# lb-charDisp-topLevel.net
KiCad netlist of a schematic drawn in Altium Designer
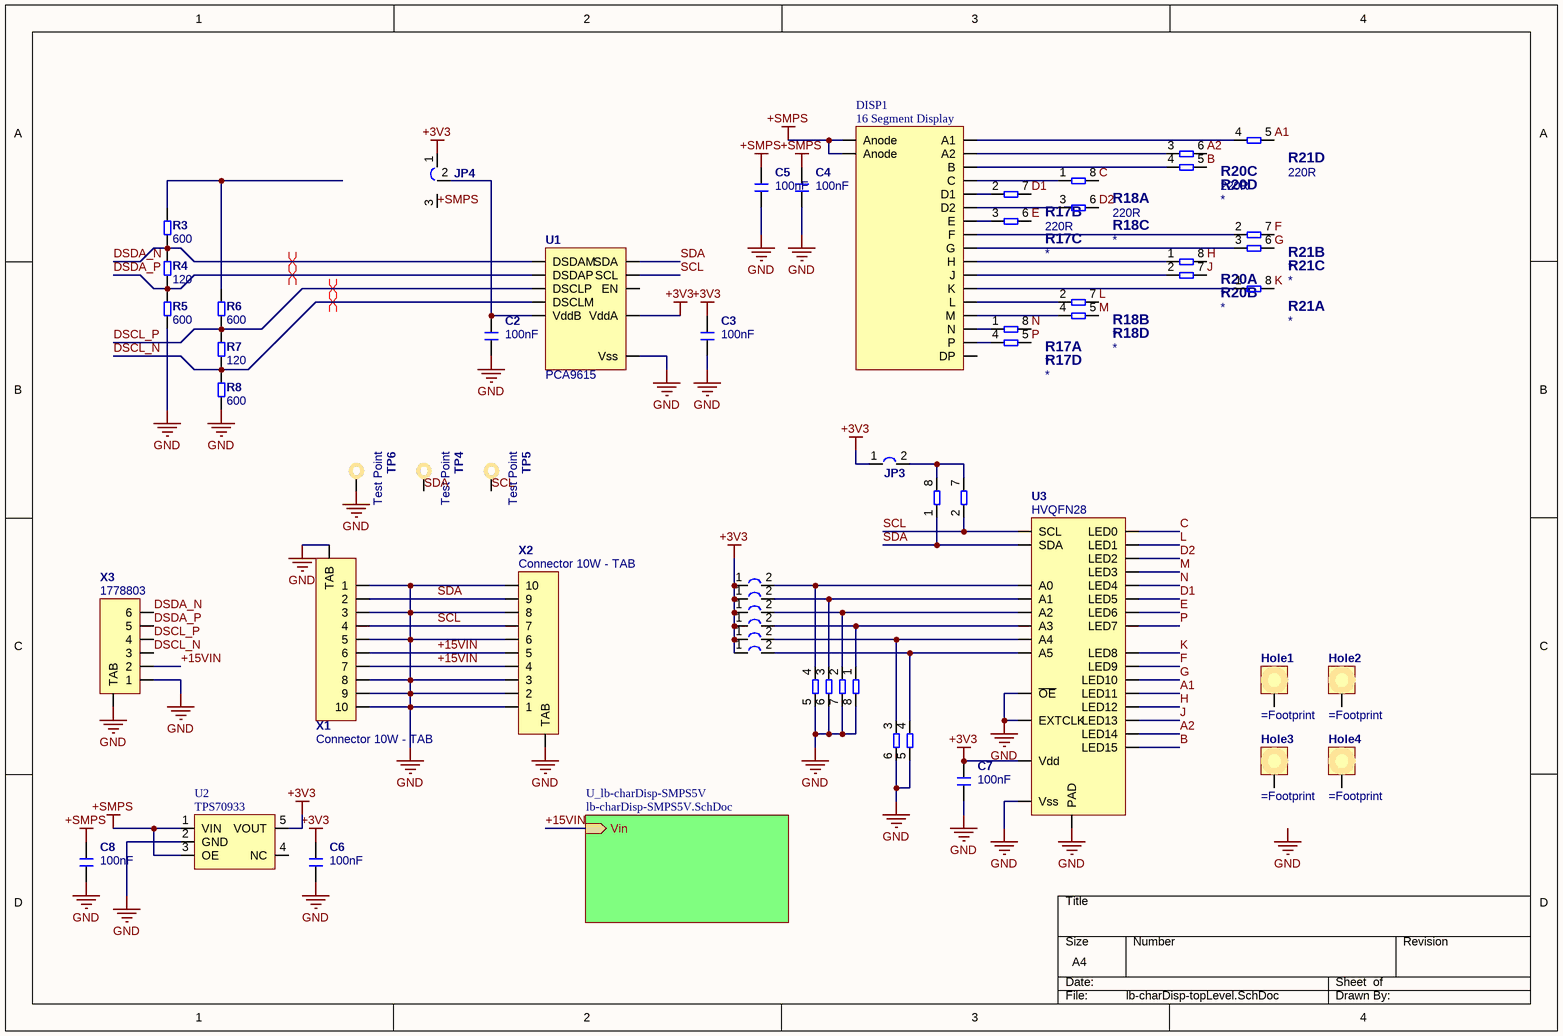
[diagram p0: lb-charDisp-topLevel.SchDoc]

(export (version "E")
  (design (tool "Eeschema 10.0.6"))
  (components
    (comp (ref "C2")
      (value "100nF")
      (footprint "C0603_N")
      (description "Capacitor MLCC")
      (fields
        (field (name "MANUFACTURER") "Yageo")
        (field (name "MANUFACTURER PART NUMBER") "CC0603KRX7R9BB104")
      )
      (libsource (lib "wes") (part "Capacitor"))
    )
    (comp (ref "C3")
      (value "100nF")
      (footprint "C0603_N")
      (description "Capacitor MLCC")
      (fields
        (field (name "MANUFACTURER") "Yageo")
        (field (name "MANUFACTURER PART NUMBER") "CC0603KRX7R9BB104")
      )
      (libsource (lib "wes") (part "Capacitor"))
    )
    (comp (ref "C4")
      (value "100nF")
      (footprint "C0603_N")
      (description "Capacitor MLCC")
      (fields
        (field (name "MANUFACTURER") "Yageo")
        (field (name "MANUFACTURER PART NUMBER") "CC0603KRX7R9BB104")
      )
      (libsource (lib "wes") (part "Capacitor"))
    )
    (comp (ref "C5")
      (value "100nF")
      (footprint "C0603_N")
      (description "Capacitor MLCC")
      (fields
        (field (name "MANUFACTURER") "Yageo")
        (field (name "MANUFACTURER PART NUMBER") "CC0603KRX7R9BB104")
      )
      (libsource (lib "wes") (part "Capacitor"))
    )
    (comp (ref "C6")
      (value "100nF")
      (footprint "C0603_N")
      (description "Capacitor MLCC")
      (fields
        (field (name "MANUFACTURER") "Yageo")
        (field (name "MANUFACTURER PART NUMBER") "CC0603KRX7R9BB104")
      )
      (libsource (lib "wes") (part "Capacitor"))
    )
    (comp (ref "C7")
      (value "100nF")
      (footprint "C0603_N")
      (description "Capacitor MLCC")
      (fields
        (field (name "MANUFACTURER") "Yageo")
        (field (name "MANUFACTURER PART NUMBER") "CC0603KRX7R9BB104")
      )
      (libsource (lib "wes") (part "Capacitor"))
    )
    (comp (ref "C8")
      (value "100nF")
      (footprint "C0603_N")
      (description "Capacitor MLCC")
      (fields
        (field (name "MANUFACTURER") "Yageo")
        (field (name "MANUFACTURER PART NUMBER") "CC0603KRX7R9BB104")
      )
      (libsource (lib "wes") (part "Capacitor"))
    )
    (comp (ref "DISP1")
      (value "16 Segment Display")
      (footprint "PSA23-11SRWA")
      (libsource (lib "wes") (part "Display 16 Segment"))
    )
    (comp (ref "Hole1") (value "~") (footprint "Insert-Thread-SMD-M2") (libsource (lib "wes") (part "Hole")))
    (comp (ref "Hole2") (value "~") (footprint "Insert-Thread-SMD-M2") (libsource (lib "wes") (part "Hole")))
    (comp (ref "Hole3") (value "~") (footprint "Insert-Thread-SMD-M2") (libsource (lib "wes") (part "Hole")))
    (comp (ref "Hole4") (value "~") (footprint "Insert-Thread-SMD-M2") (libsource (lib "wes") (part "Hole")))
    (comp (ref "JP3")
      (value "Jumper 2W")
      (footprint "Jumper SMD 2W NO")
      (libsource (lib "wes") (part "Jumper 2W"))
    )
    (comp (ref "JP4")
      (value "Jumper 3W")
      (footprint "Jumper SMD 3W NO")
      (libsource (lib "wes") (part "Jumper 3W"))
    )
    (comp (ref "JP_A0")
      (value "Jumper 2W")
      (footprint "Jumper SMD 2W NO")
      (libsource (lib "wes") (part "Jumper 2W"))
    )
    (comp (ref "JP_A1")
      (value "Jumper 2W")
      (footprint "Jumper SMD 2W NO")
      (libsource (lib "wes") (part "Jumper 2W"))
    )
    (comp (ref "JP_A2")
      (value "Jumper 2W")
      (footprint "Jumper SMD 2W NO")
      (libsource (lib "wes") (part "Jumper 2W"))
    )
    (comp (ref "JP_A3")
      (value "Jumper 2W")
      (footprint "Jumper SMD 2W NO")
      (libsource (lib "wes") (part "Jumper 2W"))
    )
    (comp (ref "JP_A4")
      (value "Jumper 2W")
      (footprint "Jumper SMD 2W NO")
      (libsource (lib "wes") (part "Jumper 2W"))
    )
    (comp (ref "JP_A5")
      (value "Jumper 2W")
      (footprint "Jumper SMD 2W NO")
      (libsource (lib "wes") (part "Jumper 2W"))
    )
    (comp (ref "R1") (value "; 4k7") (footprint "YC164") (libsource (lib "wes") (part "Resistor Array - 4P")))
    (comp (ref "R2") (value "; 4k7") (footprint "YC164") (libsource (lib "wes") (part "Resistor Array - 4P")))
    (comp (ref "R3")
      (value "600")
      (footprint "R0603")
      (fields (field (name "PUBLISHER") "Altium Limited"))
      (libsource (lib "wes") (part "Resistor"))
    )
    (comp (ref "R4")
      (value "120")
      (footprint "R0603")
      (fields (field (name "PUBLISHER") "Altium Limited"))
      (libsource (lib "wes") (part "Resistor"))
    )
    (comp (ref "R5")
      (value "600")
      (footprint "R0603")
      (fields (field (name "PUBLISHER") "Altium Limited"))
      (libsource (lib "wes") (part "Resistor"))
    )
    (comp (ref "R6")
      (value "600")
      (footprint "R0603")
      (fields (field (name "PUBLISHER") "Altium Limited"))
      (libsource (lib "wes") (part "Resistor"))
    )
    (comp (ref "R7")
      (value "120")
      (footprint "R0603")
      (fields (field (name "PUBLISHER") "Altium Limited"))
      (libsource (lib "wes") (part "Resistor"))
    )
    (comp (ref "R8")
      (value "600")
      (footprint "R0603")
      (fields (field (name "PUBLISHER") "Altium Limited"))
      (libsource (lib "wes") (part "Resistor"))
    )
    (comp (ref "R17")
      (value "Resistor Array - 4P")
      (footprint "YC164")
      (fields (field (name "ALTIUM_VALUE") "*") (field (name "Comment") "Resistor Array - 4P"))
      (libsource (lib "wes") (part "Resistor Array - 4P"))
    )
    (comp (ref "R18")
      (value "220R")
      (footprint "YC164")
      (fields (field (name "ALTIUM_VALUE") "*") (field (name "Comment") "Resistor Array - 4P"))
      (libsource (lib "wes") (part "Resistor Array - 4P"))
    )
    (comp (ref "R20")
      (value "Resistor Array - 4P")
      (footprint "YC164")
      (fields (field (name "ALTIUM_VALUE") "*") (field (name "Comment") "Resistor Array - 4P"))
      (libsource (lib "wes") (part "Resistor Array - 4P"))
    )
    (comp (ref "R21")
      (value "Resistor Array - 4P")
      (footprint "YC164")
      (fields (field (name "ALTIUM_VALUE") "*") (field (name "Comment") "Resistor Array - 4P"))
      (libsource (lib "wes") (part "Resistor Array - 4P"))
    )
    (comp (ref "TP4")
      (value "Test Point")
      (footprint "TestPoint-1.2mm")
      (libsource (lib "wes") (part "Test Point"))
    )
    (comp (ref "TP5")
      (value "Test Point")
      (footprint "TestPoint-1.2mm")
      (libsource (lib "wes") (part "Test Point"))
    )
    (comp (ref "TP6")
      (value "Test Point")
      (footprint "TestPoint-1.2mm")
      (libsource (lib "wes") (part "Test Point"))
    )
    (comp (ref "U1") (value "PCA9615") (footprint "TSSOP10") (libsource (lib "wes") (part "PCA9615DP")))
    (comp (ref "U2") (value "TPS70933") (footprint "SOT23-5_N") (libsource (lib "wes") (part "XC6222")))
    (comp (ref "U3") (value "HVQFN28") (footprint "QFN28") (libsource (lib "wes") (part "PCA9685")))
    (comp (ref "X1")
      (value "Connector 10W - TAB")
      (footprint "FPC Conn. 10W 1-84953-0")
      (libsource (lib "") (part "Connector 10W - TAB_1"))
    )
    (comp (ref "X2")
      (value "Connector 10W - TAB")
      (footprint "FPC Conn. 10W 1-84953-0")
      (libsource (lib "wes") (part "Connector 10W - TAB"))
    )
    (comp (ref "X3")
      (value "1778803")
      (footprint "PTSM-6W-H-SMD")
      (libsource (lib "wes") (part "Connector 6W - TAB"))
    )
  )
  (nets
    (net (code "1") (name "+3V3") (class "Default")
      (node (ref "C3") (pin "1") (pintype "passive"))
      (node (ref "C6") (pin "1") (pintype "passive"))
      (node (ref "C7") (pin "1") (pintype "passive"))
      (node (ref "JP3") (pin "1") (pinfunction "1_1") (pintype "passive"))
      (node (ref "JP4") (pin "1") (pinfunction "1_1") (pintype "passive"))
      (node (ref "JP_A0") (pin "1") (pinfunction "1_1") (pintype "passive"))
      (node (ref "JP_A1") (pin "1") (pinfunction "1_1") (pintype "passive"))
      (node (ref "JP_A2") (pin "1") (pinfunction "1_1") (pintype "passive"))
      (node (ref "JP_A3") (pin "1") (pinfunction "1_1") (pintype "passive"))
      (node (ref "JP_A4") (pin "1") (pinfunction "1_1") (pintype "passive"))
      (node (ref "JP_A5") (pin "1") (pinfunction "1_1") (pintype "passive"))
      (node (ref "U1") (pin "1") (pinfunction "VddA_1") (pintype "passive"))
      (node (ref "U2") (pin "5") (pinfunction "VOUT_5") (pintype "passive"))
      (node (ref "U3") (pin "25") (pinfunction "Vdd_25") (pintype "passive"))
    )
    (net (code "2") (name "+SMPS") (class "Default")
      (node (ref "C4") (pin "1") (pintype "passive"))
      (node (ref "C5") (pin "1") (pintype "passive"))
      (node (ref "C8") (pin "1") (pintype "passive"))
      (node (ref "DISP1") (pin "1") (pinfunction "Anode_1") (pintype "passive"))
      (node (ref "DISP1") (pin "11") (pinfunction "Anode_11") (pintype "passive"))
      (node (ref "JP4") (pin "3") (pinfunction "3_3") (pintype "passive"))
      (node (ref "U2") (pin "1") (pinfunction "VIN_1") (pintype "passive"))
      (node (ref "U2") (pin "3") (pinfunction "OE_3") (pintype "passive"))
    )
    (net (code "3") (name "/+15VIN") (class "Default")
      (node (ref "X1") (pin "6") (pinfunction "6_6") (pintype "passive"))
      (node (ref "X1") (pin "7") (pinfunction "7_7") (pintype "passive"))
      (node (ref "X2") (pin "4") (pinfunction "4_4") (pintype "passive"))
      (node (ref "X2") (pin "5") (pinfunction "5_5") (pintype "passive"))
      (node (ref "X3") (pin "2") (pinfunction "2_2") (pintype "power_in"))
    )
    (net (code "4") (name "/A1") (class "Default")
      (node (ref "R21") (pin "5") (pinfunction "5_5") (pintype "passive"))
      (node (ref "U3") (pin "15") (pinfunction "LED11_15") (pintype "passive"))
    )
    (net (code "5") (name "/A2") (class "Default")
      (node (ref "R20") (pin "6") (pinfunction "6_6") (pintype "passive"))
      (node (ref "U3") (pin "18") (pinfunction "LED14_18") (pintype "passive"))
    )
    (net (code "6") (name "/B") (class "Default")
      (node (ref "R20") (pin "5") (pinfunction "5_5") (pintype "passive"))
      (node (ref "U3") (pin "19") (pinfunction "LED15_19") (pintype "passive"))
    )
    (net (code "7") (name "/C") (class "Default")
      (node (ref "R18") (pin "8") (pinfunction "8_8") (pintype "passive"))
      (node (ref "U3") (pin "3") (pinfunction "LED0_3") (pintype "passive"))
    )
    (net (code "8") (name "/D1") (class "Default")
      (node (ref "R17") (pin "7") (pinfunction "7_7") (pintype "passive"))
      (node (ref "U3") (pin "8") (pinfunction "LED5_8") (pintype "passive"))
    )
    (net (code "9") (name "/D2") (class "Default")
      (node (ref "R18") (pin "6") (pinfunction "6_6") (pintype "passive"))
      (node (ref "U3") (pin "5") (pinfunction "LED2_5") (pintype "passive"))
    )
    (net (code "10") (name "/DSCL_N") (class "Default")
      (node (ref "R7") (pin "1") (pinfunction "1_1") (pintype "passive"))
      (node (ref "R8") (pin "2") (pinfunction "2_2") (pintype "passive"))
      (node (ref "U1") (pin "6") (pinfunction "DSCLM_6") (pintype "passive"))
      (node (ref "X3") (pin "3") (pinfunction "3_3") (pintype "power_in"))
    )
    (net (code "11") (name "/DSCL_P") (class "Default")
      (node (ref "R6") (pin "1") (pinfunction "1_1") (pintype "passive"))
      (node (ref "R7") (pin "2") (pinfunction "2_2") (pintype "passive"))
      (node (ref "U1") (pin "7") (pinfunction "DSCLP_7") (pintype "passive"))
      (node (ref "X3") (pin "4") (pinfunction "4_4") (pintype "power_in"))
    )
    (net (code "12") (name "/DSDA_N") (class "Default")
      (node (ref "R3") (pin "1") (pinfunction "1_1") (pintype "passive"))
      (node (ref "R4") (pin "2") (pinfunction "2_2") (pintype "passive"))
      (node (ref "U1") (pin "9") (pinfunction "DSDAM_9") (pintype "passive"))
      (node (ref "X3") (pin "6") (pinfunction "6_6") (pintype "power_in"))
    )
    (net (code "13") (name "/DSDA_P") (class "Default")
      (node (ref "R4") (pin "1") (pinfunction "1_1") (pintype "passive"))
      (node (ref "R5") (pin "2") (pinfunction "2_2") (pintype "passive"))
      (node (ref "U1") (pin "8") (pinfunction "DSDAP_8") (pintype "passive"))
      (node (ref "X3") (pin "5") (pinfunction "5_5") (pintype "power_in"))
    )
    (net (code "14") (name "/E") (class "Default")
      (node (ref "R17") (pin "6") (pinfunction "6_6") (pintype "passive"))
      (node (ref "U3") (pin "9") (pinfunction "LED6_9") (pintype "passive"))
    )
    (net (code "15") (name "/F") (class "Default")
      (node (ref "R21") (pin "7") (pinfunction "7_7") (pintype "passive"))
      (node (ref "U3") (pin "13") (pinfunction "LED9_13") (pintype "passive"))
    )
    (net (code "16") (name "/G") (class "Default")
      (node (ref "R21") (pin "6") (pinfunction "6_6") (pintype "passive"))
      (node (ref "U3") (pin "14") (pinfunction "LED10_14") (pintype "passive"))
    )
    (net (code "17") (name "/H") (class "Default")
      (node (ref "R20") (pin "8") (pinfunction "8_8") (pintype "passive"))
      (node (ref "U3") (pin "16") (pinfunction "LED12_16") (pintype "passive"))
    )
    (net (code "18") (name "/J") (class "Default")
      (node (ref "R20") (pin "7") (pinfunction "7_7") (pintype "passive"))
      (node (ref "U3") (pin "17") (pinfunction "LED13_17") (pintype "passive"))
    )
    (net (code "19") (name "/K") (class "Default")
      (node (ref "R21") (pin "8") (pinfunction "8_8") (pintype "passive"))
      (node (ref "U3") (pin "12") (pinfunction "LED8_12") (pintype "passive"))
    )
    (net (code "20") (name "/L") (class "Default")
      (node (ref "R18") (pin "7") (pinfunction "7_7") (pintype "passive"))
      (node (ref "U3") (pin "4") (pinfunction "LED1_4") (pintype "passive"))
    )
    (net (code "21") (name "/M") (class "Default")
      (node (ref "R18") (pin "5") (pinfunction "5_5") (pintype "passive"))
      (node (ref "U3") (pin "6") (pinfunction "LED3_6") (pintype "passive"))
    )
    (net (code "22") (name "/N") (class "Default")
      (node (ref "R17") (pin "8") (pinfunction "8_8") (pintype "passive"))
      (node (ref "U3") (pin "7") (pinfunction "LED4_7") (pintype "passive"))
    )
    (net (code "23") (name "/P") (class "Default")
      (node (ref "R17") (pin "5") (pinfunction "5_5") (pintype "passive"))
      (node (ref "U3") (pin "10") (pinfunction "LED7_10") (pintype "passive"))
    )
    (net (code "24") (name "/SCL") (class "Default")
      (node (ref "R2") (pin "2") (pinfunction "2_2") (pintype "passive"))
      (node (ref "TP5") (pin "1") (pinfunction "1_1") (pintype "passive"))
      (node (ref "U1") (pin "4") (pinfunction "SCL_4") (pintype "passive"))
      (node (ref "U3") (pin "23") (pinfunction "SCL_23") (pintype "passive"))
      (node (ref "X1") (pin "4") (pinfunction "4_4") (pintype "passive"))
      (node (ref "X2") (pin "7") (pinfunction "7_7") (pintype "passive"))
    )
    (net (code "25") (name "/SDA") (class "Default")
      (node (ref "R2") (pin "1") (pinfunction "1_1") (pintype "passive"))
      (node (ref "TP4") (pin "1") (pinfunction "1_1") (pintype "passive"))
      (node (ref "U1") (pin "2") (pinfunction "SDA_2") (pintype "passive"))
      (node (ref "U3") (pin "24") (pinfunction "SDA_24") (pintype "passive"))
      (node (ref "X1") (pin "2") (pinfunction "2_2") (pintype "passive"))
      (node (ref "X2") (pin "9") (pinfunction "9_9") (pintype "passive"))
    )
    (net (code "26") (name "GND") (class "Default")
      (node (ref "C2") (pin "2") (pintype "passive"))
      (node (ref "C3") (pin "2") (pintype "passive"))
      (node (ref "C4") (pin "2") (pintype "passive"))
      (node (ref "C5") (pin "2") (pintype "passive"))
      (node (ref "C6") (pin "2") (pintype "passive"))
      (node (ref "C7") (pin "2") (pintype "passive"))
      (node (ref "C8") (pin "2") (pintype "passive"))
      (node (ref "R1") (pin "5") (pinfunction "5_5") (pintype "passive"))
      (node (ref "R1") (pin "6") (pinfunction "6_6") (pintype "passive"))
      (node (ref "R1") (pin "7") (pinfunction "7_7") (pintype "passive"))
      (node (ref "R1") (pin "8") (pinfunction "8_8") (pintype "passive"))
      (node (ref "R2") (pin "5") (pinfunction "5_5") (pintype "passive"))
      (node (ref "R2") (pin "6") (pinfunction "6_6") (pintype "passive"))
      (node (ref "R5") (pin "1") (pinfunction "1_1") (pintype "passive"))
      (node (ref "R8") (pin "1") (pinfunction "1_1") (pintype "passive"))
      (node (ref "TP6") (pin "1") (pinfunction "1_1") (pintype "passive"))
      (node (ref "U1") (pin "5") (pinfunction "Vss_5") (pintype "passive"))
      (node (ref "U2") (pin "2") (pinfunction "GND_2") (pintype "passive"))
      (node (ref "U3") (pin "11") (pinfunction "Vss_11") (pintype "passive"))
      (node (ref "U3") (pin "20") (pinfunction "~{OE}_20") (pintype "passive"))
      (node (ref "U3") (pin "22") (pinfunction "EXTCLK_22") (pintype "passive"))
      (node (ref "U3") (pin "PAD") (pinfunction "PAD_PAD") (pintype "passive"))
      (node (ref "X1") (pin "1") (pinfunction "1_1") (pintype "passive"))
      (node (ref "X1") (pin "10") (pinfunction "10_10") (pintype "passive"))
      (node (ref "X1") (pin "3") (pinfunction "3_3") (pintype "passive"))
      (node (ref "X1") (pin "5") (pinfunction "5_5") (pintype "passive"))
      (node (ref "X1") (pin "8") (pinfunction "8_8") (pintype "passive"))
      (node (ref "X1") (pin "9") (pinfunction "9_9") (pintype "passive"))
      (node (ref "X1") (pin "TAB") (pinfunction "TAB_TAB") (pintype "passive"))
      (node (ref "X2") (pin "1") (pinfunction "1_1") (pintype "passive"))
      (node (ref "X2") (pin "10") (pinfunction "10_10") (pintype "passive"))
      (node (ref "X2") (pin "2") (pinfunction "2_2") (pintype "passive"))
      (node (ref "X2") (pin "3") (pinfunction "3_3") (pintype "passive"))
      (node (ref "X2") (pin "6") (pinfunction "6_6") (pintype "passive"))
      (node (ref "X2") (pin "8") (pinfunction "8_8") (pintype "passive"))
      (node (ref "X2") (pin "TAB") (pinfunction "TAB_TAB") (pintype "passive"))
      (node (ref "X3") (pin "1") (pinfunction "1_1") (pintype "power_in"))
      (node (ref "X3") (pin "TAB") (pinfunction "TAB_TAB") (pintype "power_in"))
    )
    (net (code "27") (name "Net-(DISP1-A1)") (class "Default")
      (node (ref "DISP1") (pin "17") (pinfunction "A1_17") (pintype "passive"))
      (node (ref "R21") (pin "4") (pinfunction "4_4") (pintype "passive"))
    )
    (net (code "28") (name "Net-(DISP1-A2)") (class "Default")
      (node (ref "DISP1") (pin "14") (pinfunction "A2_14") (pintype "passive"))
      (node (ref "R20") (pin "3") (pinfunction "3_3") (pintype "passive"))
    )
    (net (code "29") (name "Net-(DISP1-B)") (class "Default")
      (node (ref "DISP1") (pin "13") (pinfunction "B_13") (pintype "passive"))
      (node (ref "R20") (pin "4") (pinfunction "4_4") (pintype "passive"))
    )
    (net (code "30") (name "Net-(DISP1-C)") (class "Default")
      (node (ref "DISP1") (pin "9") (pinfunction "C_9") (pintype "passive"))
      (node (ref "R18") (pin "1") (pinfunction "1_1") (pintype "passive"))
    )
    (net (code "31") (name "Net-(DISP1-D1)") (class "Default")
      (node (ref "DISP1") (pin "4") (pinfunction "D1_4") (pintype "passive"))
      (node (ref "R17") (pin "2") (pinfunction "2_2") (pintype "passive"))
    )
    (net (code "32") (name "Net-(DISP1-D2)") (class "Default")
      (node (ref "DISP1") (pin "7") (pinfunction "D2_7") (pintype "passive"))
      (node (ref "R18") (pin "3") (pinfunction "3_3") (pintype "passive"))
    )
    (net (code "33") (name "Net-(DISP1-E)") (class "Default")
      (node (ref "DISP1") (pin "3") (pinfunction "E_3") (pintype "passive"))
      (node (ref "R17") (pin "3") (pinfunction "3_3") (pintype "passive"))
    )
    (net (code "34") (name "Net-(DISP1-F)") (class "Default")
      (node (ref "DISP1") (pin "19") (pinfunction "F_19") (pintype "passive"))
      (node (ref "R21") (pin "2") (pinfunction "2_2") (pintype "passive"))
    )
    (net (code "35") (name "Net-(DISP1-G)") (class "Default")
      (node (ref "DISP1") (pin "18") (pinfunction "G_18") (pintype "passive"))
      (node (ref "R21") (pin "3") (pinfunction "3_3") (pintype "passive"))
    )
    (net (code "36") (name "Net-(DISP1-H)") (class "Default")
      (node (ref "DISP1") (pin "16") (pinfunction "H_16") (pintype "passive"))
      (node (ref "R20") (pin "1") (pinfunction "1_1") (pintype "passive"))
    )
    (net (code "37") (name "Net-(DISP1-J)") (class "Default")
      (node (ref "DISP1") (pin "15") (pinfunction "J_15") (pintype "passive"))
      (node (ref "R20") (pin "2") (pinfunction "2_2") (pintype "passive"))
    )
    (net (code "38") (name "Net-(DISP1-K)") (class "Default")
      (node (ref "DISP1") (pin "12") (pinfunction "K_12") (pintype "passive"))
      (node (ref "R21") (pin "1") (pinfunction "1_1") (pintype "passive"))
    )
    (net (code "39") (name "Net-(DISP1-L)") (class "Default")
      (node (ref "DISP1") (pin "8") (pinfunction "L_8") (pintype "passive"))
      (node (ref "R18") (pin "2") (pinfunction "2_2") (pintype "passive"))
    )
    (net (code "40") (name "Net-(DISP1-M)") (class "Default")
      (node (ref "DISP1") (pin "6") (pinfunction "M_6") (pintype "passive"))
      (node (ref "R18") (pin "4") (pinfunction "4_4") (pintype "passive"))
    )
    (net (code "41") (name "Net-(DISP1-N)") (class "Default")
      (node (ref "DISP1") (pin "5") (pinfunction "N_5") (pintype "passive"))
      (node (ref "R17") (pin "1") (pinfunction "1_1") (pintype "passive"))
    )
    (net (code "42") (name "Net-(DISP1-P)") (class "Default")
      (node (ref "DISP1") (pin "2") (pinfunction "P_2") (pintype "passive"))
      (node (ref "R17") (pin "4") (pinfunction "4_4") (pintype "passive"))
    )
    (net (code "43") (name "Net-(JP3-Pad2)") (class "Default")
      (node (ref "JP3") (pin "2") (pinfunction "2_2") (pintype "passive"))
      (node (ref "R2") (pin "7") (pinfunction "7_7") (pintype "passive"))
      (node (ref "R2") (pin "8") (pinfunction "8_8") (pintype "passive"))
    )
    (net (code "44") (name "Net-(R3-Pad2)") (class "Default")
      (node (ref "R3") (pin "2") (pinfunction "2_2") (pintype "passive"))
      (node (ref "R6") (pin "2") (pinfunction "2_2") (pintype "passive"))
    )
    (net (code "45") (name "Net-(U1-VddB)") (class "Default")
      (node (ref "C2") (pin "1") (pintype "passive"))
      (node (ref "JP4") (pin "2") (pinfunction "2_2") (pintype "passive"))
      (node (ref "U1") (pin "10") (pinfunction "VddB_10") (pintype "passive"))
    )
    (net (code "46") (name "Net-(U3-A0)") (class "Default")
      (node (ref "JP_A0") (pin "2") (pinfunction "2_2") (pintype "passive"))
      (node (ref "R1") (pin "4") (pinfunction "4_4") (pintype "passive"))
      (node (ref "U3") (pin "26") (pinfunction "A0_26") (pintype "passive"))
    )
    (net (code "47") (name "Net-(U3-A1)") (class "Default")
      (node (ref "JP_A1") (pin "2") (pinfunction "2_2") (pintype "passive"))
      (node (ref "R1") (pin "3") (pinfunction "3_3") (pintype "passive"))
      (node (ref "U3") (pin "27") (pinfunction "A1_27") (pintype "passive"))
    )
    (net (code "48") (name "Net-(U3-A2)") (class "Default")
      (node (ref "JP_A2") (pin "2") (pinfunction "2_2") (pintype "passive"))
      (node (ref "R1") (pin "2") (pinfunction "2_2") (pintype "passive"))
      (node (ref "U3") (pin "28") (pinfunction "A2_28") (pintype "passive"))
    )
    (net (code "49") (name "Net-(U3-A3)") (class "Default")
      (node (ref "JP_A3") (pin "2") (pinfunction "2_2") (pintype "passive"))
      (node (ref "R1") (pin "1") (pinfunction "1_1") (pintype "passive"))
      (node (ref "U3") (pin "1") (pinfunction "A3_1") (pintype "passive"))
    )
    (net (code "50") (name "Net-(U3-A4)") (class "Default")
      (node (ref "JP_A4") (pin "2") (pinfunction "2_2") (pintype "passive"))
      (node (ref "R2") (pin "3") (pinfunction "3_3") (pintype "passive"))
      (node (ref "U3") (pin "2") (pinfunction "A4_2") (pintype "passive"))
    )
    (net (code "51") (name "Net-(U3-A5)") (class "Default")
      (node (ref "JP_A5") (pin "2") (pinfunction "2_2") (pintype "passive"))
      (node (ref "R2") (pin "4") (pinfunction "4_4") (pintype "passive"))
      (node (ref "U3") (pin "21") (pinfunction "A5_21") (pintype "passive"))
    )
    (net (code "52") (name "unconnected-(DISP1-DP-Pad10)") (class "Default")
      (node (ref "DISP1") (pin "10") (pinfunction "DP_10") (pintype "passive"))
    )
    (net (code "53") (name "unconnected-(Hole1-Pad1)") (class "Default")
      (node (ref "Hole1") (pin "1") (pinfunction "1_1") (pintype "passive"))
    )
    (net (code "54") (name "unconnected-(Hole2-Pad1)") (class "Default")
      (node (ref "Hole2") (pin "1") (pinfunction "1_1") (pintype "passive"))
    )
    (net (code "55") (name "unconnected-(Hole3-Pad1)") (class "Default")
      (node (ref "Hole3") (pin "1") (pinfunction "1_1") (pintype "passive"))
    )
    (net (code "56") (name "unconnected-(Hole4-Pad1)") (class "Default")
      (node (ref "Hole4") (pin "1") (pinfunction "1_1") (pintype "passive"))
    )
    (net (code "57") (name "unconnected-(U1-EN-Pad3)") (class "Default")
      (node (ref "U1") (pin "3") (pinfunction "EN_3") (pintype "passive"))
    )
    (net (code "58") (name "unconnected-(U2-NC-Pad4)") (class "Default")
      (node (ref "U2") (pin "4") (pinfunction "NC_4") (pintype "passive"))
    )
  )
)
